# Adafruit_DPI_Kippah.net
KiCad netlist of a schematic drawn in EAGLE
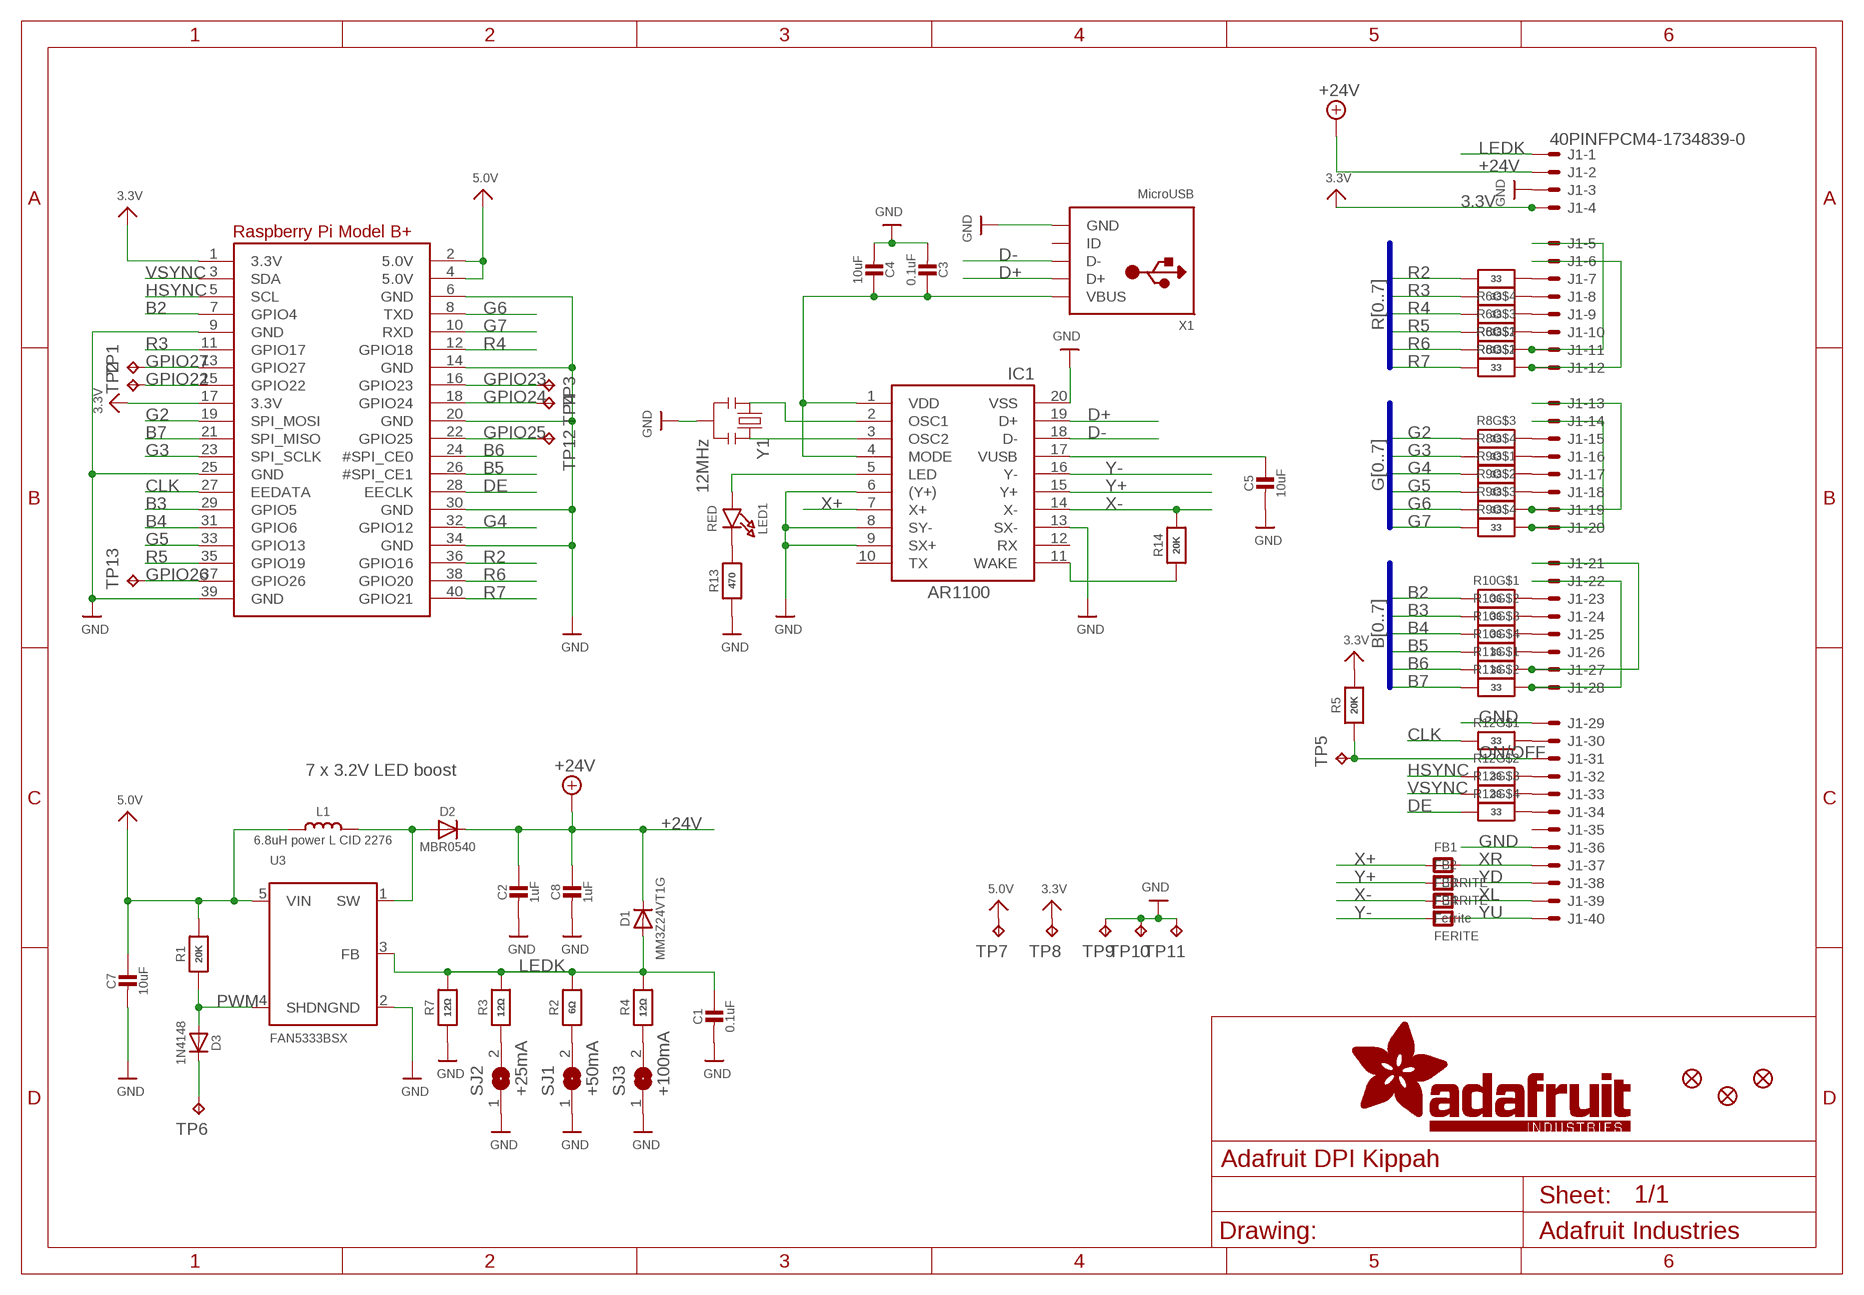
[diagram p0: schematic, sheet 1]

(export (version "E")
  (design (tool "Eeschema 10.0.6"))
  (components
    (comp (ref "C1")
      (value "0.1uF")
      (footprint "eagle-import:0805-NO")
      (libsource (lib "eagle-import") (part "CAP_CERAMIC0805-NOOUTLINE"))
    )
    (comp (ref "C2")
      (value "1uF")
      (footprint "eagle-import:_0805MP")
      (libsource (lib "eagle-import") (part "CAP_CERAMIC_0805MP"))
    )
    (comp (ref "C3")
      (value "0.1uF")
      (footprint "eagle-import:0805-NO")
      (libsource (lib "eagle-import") (part "CAP_CERAMIC0805-NOOUTLINE"))
    )
    (comp (ref "C4")
      (value "10uF")
      (footprint "eagle-import:0805-NO")
      (libsource (lib "eagle-import") (part "CAP_CERAMIC0805-NOOUTLINE"))
    )
    (comp (ref "C5")
      (value "10uF")
      (footprint "eagle-import:0805-NO")
      (libsource (lib "eagle-import") (part "CAP_CERAMIC0805-NOOUTLINE"))
    )
    (comp (ref "C7")
      (value "10uF")
      (footprint "eagle-import:0805-NO")
      (libsource (lib "eagle-import") (part "CAP_CERAMIC0805-NOOUTLINE"))
    )
    (comp (ref "C8")
      (value "1uF")
      (footprint "eagle-import:0805-NO")
      (libsource (lib "eagle-import") (part "CAP_CERAMIC0805-NOOUTLINE"))
    )
    (comp (ref "D1")
      (value "MM3Z24VT1G")
      (footprint "eagle-import:SMADIODE")
      (libsource (lib "eagle-import") (part "DIODESMA"))
    )
    (comp (ref "D2")
      (value "MBR0540")
      (footprint "eagle-import:SOD-123")
      (libsource (lib "eagle-import") (part "DIODESOD-123"))
    )
    (comp (ref "D3")
      (value "1N4148")
      (footprint "eagle-import:SOD-323")
      (libsource (lib "eagle-import") (part "DIODESOD-323"))
    )
    (comp (ref "FB1")
      (value "FERRITE")
      (footprint "eagle-import:_0805MP")
      (libsource (lib "eagle-import") (part "FERRITE_0805MP"))
    )
    (comp (ref "FB2")
      (value "FERRITE")
      (footprint "eagle-import:_0805MP")
      (libsource (lib "eagle-import") (part "FERRITE_0805MP"))
    )
    (comp (ref "FB3")
      (value "Ferrite")
      (footprint "eagle-import:_0805MP")
      (libsource (lib "eagle-import") (part "FERRITE_0805MP"))
    )
    (comp (ref "FB4")
      (value "FERITE")
      (footprint "eagle-import:_0805MP")
      (libsource (lib "eagle-import") (part "FERRITE_0805MP"))
    )
    (comp (ref "FID1")
      (value "FIDUCIAL\"\"")
      (footprint "eagle-import:FIDUCIAL_1MM")
      (libsource (lib "eagle-import") (part "FIDUCIAL{dblquote}{dblquote}"))
    )
    (comp (ref "FID2")
      (value "FIDUCIAL\"\"")
      (footprint "eagle-import:FIDUCIAL_1MM")
      (libsource (lib "eagle-import") (part "FIDUCIAL{dblquote}{dblquote}"))
    )
    (comp (ref "FID3")
      (value "FIDUCIAL\"\"")
      (footprint "eagle-import:FIDUCIAL_1MM")
      (libsource (lib "eagle-import") (part "FIDUCIAL{dblquote}{dblquote}"))
    )
    (comp (ref "IC1")
      (value "AR1100_SSOP")
      (footprint "eagle-import:TSSOP20-5.3MMBODY")
      (libsource (lib "eagle-import") (part "AR1100_SSOP"))
    )
    (comp (ref "J1")
      (value "40PINFPCM4-1734839-0")
      (footprint "eagle-import:4-1734839-0")
      (libsource (lib "eagle-import") (part "40PINFPC4-1734839-0M"))
    )
    (comp (ref "L1")
      (value "6.8uH power L CID 2276")
      (footprint "eagle-import:INDUCTOR_5X5MM_NR5040_NOTHERMALS")
      (libsource (lib "eagle-import") (part "INDUCTORNR5040"))
    )
    (comp (ref "LED1")
      (value "RED")
      (footprint "eagle-import:CHIPLED_0805_NOOUTLINE")
      (libsource (lib "eagle-import") (part "LED0805_NOOUTLINE"))
    )
    (comp (ref "R1")
      (value "20K")
      (footprint "eagle-import:0805-NO")
      (libsource (lib "eagle-import") (part "RESISTOR0805_NOOUTLINE"))
    )
    (comp (ref "R2")
      (value "6Ω")
      (footprint "eagle-import:0805-NO")
      (libsource (lib "eagle-import") (part "RESISTOR0805_NOOUTLINE"))
    )
    (comp (ref "R3")
      (value "12Ω")
      (footprint "eagle-import:0805-NO")
      (libsource (lib "eagle-import") (part "RESISTOR0805_NOOUTLINE"))
    )
    (comp (ref "R4")
      (value "12Ω")
      (footprint "eagle-import:0805-NO")
      (libsource (lib "eagle-import") (part "RESISTOR0805_NOOUTLINE"))
    )
    (comp (ref "R5")
      (value "20K")
      (footprint "eagle-import:_0805MP")
      (libsource (lib "eagle-import") (part "RESISTOR_0805MP"))
    )
    (comp (ref "R6")
      (value "33")
      (footprint "eagle-import:RESPACK_4X0603")
      (libsource (lib "eagle-import") (part "RESISTOR_4PACK"))
    )
    (comp (ref "R7")
      (value "12Ω")
      (footprint "eagle-import:0805-NO")
      (libsource (lib "eagle-import") (part "RESISTOR0805_NOOUTLINE"))
    )
    (comp (ref "R8")
      (value "33")
      (footprint "eagle-import:RESPACK_4X0603")
      (libsource (lib "eagle-import") (part "RESISTOR_4PACK"))
    )
    (comp (ref "R9")
      (value "33")
      (footprint "eagle-import:RESPACK_4X0603")
      (libsource (lib "eagle-import") (part "RESISTOR_4PACK"))
    )
    (comp (ref "R10")
      (value "33")
      (footprint "eagle-import:RESPACK_4X0603")
      (libsource (lib "eagle-import") (part "RESISTOR_4PACK"))
    )
    (comp (ref "R11")
      (value "33")
      (footprint "eagle-import:RESPACK_4X0603")
      (libsource (lib "eagle-import") (part "RESISTOR_4PACK"))
    )
    (comp (ref "R12")
      (value "33")
      (footprint "eagle-import:RESPACK_4X0603")
      (libsource (lib "eagle-import") (part "RESISTOR_4PACK"))
    )
    (comp (ref "R13")
      (value "470")
      (footprint "eagle-import:0805-NO")
      (libsource (lib "eagle-import") (part "RESISTOR0805_NOOUTLINE"))
    )
    (comp (ref "R14")
      (value "20K")
      (footprint "eagle-import:0805-NO")
      (libsource (lib "eagle-import") (part "RESISTOR0805_NOOUTLINE"))
    )
    (comp (ref "RPI1")
      (value "RASPBERRYPI_BPLUS-SMT+SLOTS")
      (footprint "eagle-import:PI_HAT_SMT_SLOTS")
      (libsource (lib "eagle-import") (part "RASPBERRYPI_BPLUS-SMT+SLOTS"))
    )
    (comp (ref "SJ1")
      (value "+50mA")
      (footprint "eagle-import:SOLDERJUMPER_ARROW_NOPASTE")
      (libsource (lib "eagle-import") (part "SOLDERJUMPER"))
    )
    (comp (ref "SJ2")
      (value "+25mA")
      (footprint "eagle-import:SOLDERJUMPER_ARROW_NOPASTE")
      (libsource (lib "eagle-import") (part "SOLDERJUMPER"))
    )
    (comp (ref "SJ3")
      (value "+100mA")
      (footprint "eagle-import:SOLDERJUMPER_ARROW_NOPASTE")
      (libsource (lib "eagle-import") (part "SOLDERJUMPER"))
    )
    (comp (ref "TP1")
      (value "TPTP15SQ")
      (footprint "eagle-import:TP15SQ")
      (libsource (lib "eagle-import") (part "TPTP15SQ"))
    )
    (comp (ref "TP2")
      (value "TPTP15SQ")
      (footprint "eagle-import:TP15SQ")
      (libsource (lib "eagle-import") (part "TPTP15SQ"))
    )
    (comp (ref "TP3")
      (value "TPTP15SQ")
      (footprint "eagle-import:TP15SQ")
      (libsource (lib "eagle-import") (part "TPTP15SQ"))
    )
    (comp (ref "TP4")
      (value "TPTP15SQ")
      (footprint "eagle-import:TP15SQ")
      (libsource (lib "eagle-import") (part "TPTP15SQ"))
    )
    (comp (ref "TP5")
      (value "TPTP15SQ")
      (footprint "eagle-import:TP15SQ")
      (libsource (lib "eagle-import") (part "TPTP15SQ"))
    )
    (comp (ref "TP6")
      (value "TPTP15SQ")
      (footprint "eagle-import:TP15SQ")
      (libsource (lib "eagle-import") (part "TPTP15SQ"))
    )
    (comp (ref "TP7")
      (value "TPTP15SQ")
      (footprint "eagle-import:TP15SQ")
      (libsource (lib "eagle-import") (part "TPTP15SQ"))
    )
    (comp (ref "TP8")
      (value "TPTP15SQ")
      (footprint "eagle-import:TP15SQ")
      (libsource (lib "eagle-import") (part "TPTP15SQ"))
    )
    (comp (ref "TP9")
      (value "TPTP15SQ")
      (footprint "eagle-import:TP15SQ")
      (libsource (lib "eagle-import") (part "TPTP15SQ"))
    )
    (comp (ref "TP10")
      (value "TPTP15SQ")
      (footprint "eagle-import:TP15SQ")
      (libsource (lib "eagle-import") (part "TPTP15SQ"))
    )
    (comp (ref "TP11")
      (value "TPTP15SQ")
      (footprint "eagle-import:TP15SQ")
      (libsource (lib "eagle-import") (part "TPTP15SQ"))
    )
    (comp (ref "TP12")
      (value "TPTP15SQ")
      (footprint "eagle-import:TP15SQ")
      (libsource (lib "eagle-import") (part "TPTP15SQ"))
    )
    (comp (ref "TP13")
      (value "TPTP15SQ")
      (footprint "eagle-import:TP15SQ")
      (libsource (lib "eagle-import") (part "TPTP15SQ"))
    )
    (comp (ref "U3")
      (value "FAN5333BSX")
      (footprint "eagle-import:SOT23-5@1")
      (libsource (lib "eagle-import") (part "FAN5331"))
    )
    (comp (ref "X1")
      (value "MicroUSB")
      (footprint "eagle-import:4UCONN_20329")
      (libsource (lib "eagle-import") (part "USBMICRO_20329"))
    )
    (comp (ref "Y1")
      (value "12MHz")
      (footprint "eagle-import:RESONATOR-SMD")
      (libsource (lib "eagle-import") (part "RESONATORSMD"))
    )
  )
  (nets
    (net (code "7") (name "+24V") (class "Default")
      (node (ref "C2") (pin "1") (pinfunction "1_1") (pintype "passive"))
      (node (ref "C8") (pin "1") (pinfunction "1_1") (pintype "passive"))
      (node (ref "D1") (pin "C") (pinfunction "C_C") (pintype "passive"))
      (node (ref "D2") (pin "C") (pinfunction "C_C") (pintype "passive"))
      (node (ref "J1") (pin "2") (pinfunction "MS_2") (pintype "passive"))
    )
    (net (code "8") (name "/B2") (class "Default")
      (node (ref "R10") (pin "1") (pinfunction "1_1") (pintype "passive"))
      (node (ref "RPI1") (pin "7") (pinfunction "GPIO4_7") (pintype "bidirectional"))
    )
    (net (code "9") (name "/B3") (class "Default")
      (node (ref "R10") (pin "2") (pinfunction "1_2") (pintype "passive"))
      (node (ref "RPI1") (pin "29") (pinfunction "GPIO5_29") (pintype "bidirectional"))
    )
    (net (code "10") (name "/B4") (class "Default")
      (node (ref "R10") (pin "3") (pinfunction "1_3") (pintype "passive"))
      (node (ref "RPI1") (pin "31") (pinfunction "GPIO6_31") (pintype "bidirectional"))
    )
    (net (code "11") (name "/B5") (class "Default")
      (node (ref "R10") (pin "4") (pinfunction "1_4") (pintype "passive"))
      (node (ref "RPI1") (pin "26") (pinfunction "#SPI_CE1_26") (pintype "bidirectional"))
    )
    (net (code "12") (name "/B6") (class "Default")
      (node (ref "R11") (pin "1") (pinfunction "1_1") (pintype "passive"))
      (node (ref "RPI1") (pin "24") (pinfunction "#SPI_CE0_24") (pintype "bidirectional"))
    )
    (net (code "13") (name "/B7") (class "Default")
      (node (ref "R11") (pin "2") (pinfunction "1_2") (pintype "passive"))
      (node (ref "RPI1") (pin "21") (pinfunction "SPI_MISO_21") (pintype "bidirectional"))
    )
    (net (code "15") (name "/CLK") (class "Default")
      (node (ref "R12") (pin "1") (pinfunction "1_1") (pintype "passive"))
      (node (ref "RPI1") (pin "27") (pinfunction "EEDATA_27") (pintype "bidirectional"))
    )
    (net (code "16") (name "/D+") (class "Default")
      (node (ref "IC1") (pin "19") (pinfunction "D+_19") (pintype "bidirectional"))
      (node (ref "X1") (pin "D+") (pinfunction "D+_D+") (pintype "bidirectional"))
    )
    (net (code "17") (name "/D-") (class "Default")
      (node (ref "IC1") (pin "18") (pinfunction "D-_18") (pintype "bidirectional"))
      (node (ref "X1") (pin "D-") (pinfunction "D-_D-") (pintype "bidirectional"))
    )
    (net (code "18") (name "/DE") (class "Default")
      (node (ref "R12") (pin "4") (pinfunction "1_4") (pintype "passive"))
      (node (ref "RPI1") (pin "28") (pinfunction "EECLK_28") (pintype "bidirectional"))
    )
    (net (code "19") (name "/G2") (class "Default")
      (node (ref "R8") (pin "3") (pinfunction "1_3") (pintype "passive"))
      (node (ref "RPI1") (pin "19") (pinfunction "SPI_MOSI_19") (pintype "bidirectional"))
    )
    (net (code "20") (name "/G3") (class "Default")
      (node (ref "R8") (pin "4") (pinfunction "1_4") (pintype "passive"))
      (node (ref "RPI1") (pin "23") (pinfunction "SPI_SCLK_23") (pintype "bidirectional"))
    )
    (net (code "21") (name "/G4") (class "Default")
      (node (ref "R9") (pin "1") (pinfunction "1_1") (pintype "passive"))
      (node (ref "RPI1") (pin "32") (pinfunction "GPIO12_32") (pintype "bidirectional"))
    )
    (net (code "22") (name "/G5") (class "Default")
      (node (ref "R9") (pin "2") (pinfunction "1_2") (pintype "passive"))
      (node (ref "RPI1") (pin "33") (pinfunction "GPIO13_33") (pintype "bidirectional"))
    )
    (net (code "23") (name "/G6") (class "Default")
      (node (ref "R9") (pin "3") (pinfunction "1_3") (pintype "passive"))
      (node (ref "RPI1") (pin "8") (pinfunction "TXD_8") (pintype "bidirectional"))
    )
    (net (code "24") (name "/G7") (class "Default")
      (node (ref "R9") (pin "4") (pinfunction "1_4") (pintype "passive"))
      (node (ref "RPI1") (pin "10") (pinfunction "RXD_10") (pintype "bidirectional"))
    )
    (net (code "25") (name "/GPIO22") (class "Default")
      (node (ref "RPI1") (pin "15") (pinfunction "GPIO22_15") (pintype "bidirectional"))
      (node (ref "TP2") (pin "TP") (pinfunction "TP_TP") (pintype "input"))
    )
    (net (code "26") (name "/GPIO23") (class "Default")
      (node (ref "RPI1") (pin "16") (pinfunction "GPIO23_16") (pintype "bidirectional"))
      (node (ref "TP3") (pin "TP") (pinfunction "TP_TP") (pintype "input"))
    )
    (net (code "27") (name "/GPIO24") (class "Default")
      (node (ref "RPI1") (pin "18") (pinfunction "GPIO24_18") (pintype "bidirectional"))
      (node (ref "TP4") (pin "TP") (pinfunction "TP_TP") (pintype "input"))
    )
    (net (code "28") (name "/GPIO25") (class "Default")
      (node (ref "RPI1") (pin "22") (pinfunction "GPIO25_22") (pintype "bidirectional"))
      (node (ref "TP12") (pin "TP") (pinfunction "TP_TP") (pintype "input"))
    )
    (net (code "29") (name "/GPIO26") (class "Default")
      (node (ref "RPI1") (pin "37") (pinfunction "GPIO26_37") (pintype "bidirectional"))
      (node (ref "TP13") (pin "TP") (pinfunction "TP_TP") (pintype "input"))
    )
    (net (code "30") (name "/GPIO27") (class "Default")
      (node (ref "RPI1") (pin "13") (pinfunction "GPIO27_13") (pintype "bidirectional"))
      (node (ref "TP1") (pin "TP") (pinfunction "TP_TP") (pintype "input"))
    )
    (net (code "32") (name "/HSYNC") (class "Default")
      (node (ref "R12") (pin "2") (pinfunction "1_2") (pintype "passive"))
      (node (ref "RPI1") (pin "5") (pinfunction "SCL_5") (pintype "bidirectional"))
    )
    (net (code "33") (name "/LEDK") (class "Default")
      (node (ref "C1") (pin "1") (pinfunction "1_1") (pintype "passive"))
      (node (ref "D1") (pin "A") (pinfunction "A_A") (pintype "passive"))
      (node (ref "J1") (pin "1") (pinfunction "MSV_1") (pintype "passive"))
      (node (ref "R2") (pin "2") (pinfunction "2_2") (pintype "passive"))
      (node (ref "R3") (pin "2") (pinfunction "2_2") (pintype "passive"))
      (node (ref "R4") (pin "2") (pinfunction "2_2") (pintype "passive"))
      (node (ref "R7") (pin "2") (pinfunction "2_2") (pintype "passive"))
      (node (ref "U3") (pin "3") (pinfunction "FB_3") (pintype "bidirectional"))
    )
    (net (code "34") (name "/ON{slash}OFF") (class "Default")
      (node (ref "J1") (pin "31") (pinfunction "MS_31") (pintype "passive"))
      (node (ref "R5") (pin "1") (pinfunction "1_1") (pintype "passive"))
      (node (ref "TP5") (pin "TP") (pinfunction "TP_TP") (pintype "input"))
    )
    (net (code "35") (name "/PWM") (class "Default")
      (node (ref "D3") (pin "A") (pinfunction "A_A") (pintype "passive"))
      (node (ref "R1") (pin "1") (pinfunction "1_1") (pintype "passive"))
      (node (ref "U3") (pin "4") (pinfunction "SHDN_4") (pintype "bidirectional"))
    )
    (net (code "36") (name "/R2") (class "Default")
      (node (ref "R6") (pin "5") (pinfunction "2_5") (pintype "passive"))
      (node (ref "RPI1") (pin "36") (pinfunction "GPIO16_36") (pintype "bidirectional"))
    )
    (net (code "37") (name "/R3") (class "Default")
      (node (ref "R6") (pin "6") (pinfunction "2_6") (pintype "passive"))
      (node (ref "RPI1") (pin "11") (pinfunction "GPIO17_11") (pintype "bidirectional"))
    )
    (net (code "38") (name "/R4") (class "Default")
      (node (ref "R6") (pin "7") (pinfunction "2_7") (pintype "passive"))
      (node (ref "RPI1") (pin "12") (pinfunction "GPIO18_12") (pintype "bidirectional"))
    )
    (net (code "39") (name "/R5") (class "Default")
      (node (ref "R6") (pin "8") (pinfunction "2_8") (pintype "passive"))
      (node (ref "RPI1") (pin "35") (pinfunction "GPIO19_35") (pintype "bidirectional"))
    )
    (net (code "40") (name "/R6") (class "Default")
      (node (ref "R8") (pin "1") (pinfunction "1_1") (pintype "passive"))
      (node (ref "RPI1") (pin "38") (pinfunction "GPIO20_38") (pintype "bidirectional"))
    )
    (net (code "41") (name "/R7") (class "Default")
      (node (ref "R8") (pin "2") (pinfunction "1_2") (pintype "passive"))
      (node (ref "RPI1") (pin "40") (pinfunction "GPIO21_40") (pintype "bidirectional"))
    )
    (net (code "43") (name "/VSYNC") (class "Default")
      (node (ref "R12") (pin "3") (pinfunction "1_3") (pintype "passive"))
      (node (ref "RPI1") (pin "3") (pinfunction "SDA_3") (pintype "bidirectional"))
    )
    (net (code "44") (name "/X+") (class "Default")
      (node (ref "FB1") (pin "1") (pinfunction "P$1_1") (pintype "passive"))
      (node (ref "IC1") (pin "7") (pinfunction "X+_7") (pintype "bidirectional"))
    )
    (net (code "45") (name "/X-") (class "Default")
      (node (ref "FB3") (pin "1") (pinfunction "P$1_1") (pintype "passive"))
      (node (ref "IC1") (pin "14") (pinfunction "X-_14") (pintype "bidirectional"))
      (node (ref "R14") (pin "2") (pinfunction "2_2") (pintype "passive"))
    )
    (net (code "46") (name "/XL") (class "Default")
      (node (ref "FB3") (pin "2") (pinfunction "P$2_2") (pintype "passive"))
      (node (ref "J1") (pin "39") (pinfunction "MS_39") (pintype "passive"))
    )
    (net (code "47") (name "/XR") (class "Default")
      (node (ref "FB1") (pin "2") (pinfunction "P$2_2") (pintype "passive"))
      (node (ref "J1") (pin "37") (pinfunction "MS_37") (pintype "passive"))
    )
    (net (code "48") (name "/Y+") (class "Default")
      (node (ref "FB2") (pin "1") (pinfunction "P$1_1") (pintype "passive"))
      (node (ref "IC1") (pin "15") (pinfunction "Y+_15") (pintype "bidirectional"))
    )
    (net (code "49") (name "/Y-") (class "Default")
      (node (ref "FB4") (pin "1") (pinfunction "P$1_1") (pintype "passive"))
      (node (ref "IC1") (pin "16") (pinfunction "Y-_16") (pintype "bidirectional"))
    )
    (net (code "50") (name "/YD") (class "Default")
      (node (ref "FB2") (pin "2") (pinfunction "P$2_2") (pintype "passive"))
      (node (ref "J1") (pin "38") (pinfunction "MS_38") (pintype "passive"))
    )
    (net (code "51") (name "/YU") (class "Default")
      (node (ref "FB4") (pin "2") (pinfunction "P$2_2") (pintype "passive"))
      (node (ref "J1") (pin "40") (pinfunction "MS_40") (pintype "passive"))
    )
    (net (code "52") (name "3.3V") (class "Default")
      (node (ref "J1") (pin "4") (pinfunction "MS_4") (pintype "passive"))
      (node (ref "R5") (pin "2") (pinfunction "2_2") (pintype "passive"))
      (node (ref "RPI1") (pin "1") (pinfunction "3.3V_1") (pintype "power_in"))
      (node (ref "RPI1") (pin "17") (pinfunction "3.3V_17") (pintype "power_in"))
      (node (ref "TP8") (pin "TP") (pinfunction "TP_TP") (pintype "input"))
    )
    (net (code "53") (name "5.0V") (class "Default")
      (node (ref "C7") (pin "1") (pinfunction "1_1") (pintype "passive"))
      (node (ref "L1") (pin "P$1") (pinfunction "1_P$1") (pintype "passive"))
      (node (ref "R1") (pin "2") (pinfunction "2_2") (pintype "passive"))
      (node (ref "RPI1") (pin "2") (pinfunction "5.0V_2") (pintype "power_in"))
      (node (ref "RPI1") (pin "4") (pinfunction "5.0V_4") (pintype "power_in"))
      (node (ref "TP7") (pin "TP") (pinfunction "TP_TP") (pintype "input"))
      (node (ref "U3") (pin "5") (pinfunction "VIN_5") (pintype "bidirectional"))
    )
    (net (code "54") (name "GND") (class "Default")
      (node (ref "C1") (pin "2") (pinfunction "2_2") (pintype "passive"))
      (node (ref "C2") (pin "2") (pinfunction "2_2") (pintype "passive"))
      (node (ref "C3") (pin "2") (pinfunction "2_2") (pintype "passive"))
      (node (ref "C4") (pin "2") (pinfunction "2_2") (pintype "passive"))
      (node (ref "C5") (pin "2") (pinfunction "2_2") (pintype "passive"))
      (node (ref "C7") (pin "2") (pinfunction "2_2") (pintype "passive"))
      (node (ref "C8") (pin "2") (pinfunction "2_2") (pintype "passive"))
      (node (ref "IC1") (pin "13") (pinfunction "SX-_13") (pintype "bidirectional"))
      (node (ref "IC1") (pin "20") (pinfunction "VSS_20") (pintype "power_in"))
      (node (ref "IC1") (pin "6") (pinfunction "(Y+)_6") (pintype "bidirectional"))
      (node (ref "IC1") (pin "8") (pinfunction "SY-_8") (pintype "bidirectional"))
      (node (ref "IC1") (pin "9") (pinfunction "SX+_9") (pintype "bidirectional"))
      (node (ref "J1") (pin "29") (pinfunction "MS_29") (pintype "passive"))
      (node (ref "J1") (pin "3") (pinfunction "MS_3") (pintype "passive"))
      (node (ref "J1") (pin "36") (pinfunction "MS_36") (pintype "passive"))
      (node (ref "R13") (pin "1") (pinfunction "1_1") (pintype "passive"))
      (node (ref "R7") (pin "1") (pinfunction "1_1") (pintype "passive"))
      (node (ref "RPI1") (pin "14") (pinfunction "GND_14") (pintype "power_in"))
      (node (ref "RPI1") (pin "20") (pinfunction "GND_20") (pintype "power_in"))
      (node (ref "RPI1") (pin "25") (pinfunction "GND_25") (pintype "power_in"))
      (node (ref "RPI1") (pin "30") (pinfunction "GND_30") (pintype "power_in"))
      (node (ref "RPI1") (pin "34") (pinfunction "GND_34") (pintype "power_in"))
      (node (ref "RPI1") (pin "39") (pinfunction "GND_39") (pintype "power_in"))
      (node (ref "RPI1") (pin "6") (pinfunction "GND_6") (pintype "power_in"))
      (node (ref "RPI1") (pin "9") (pinfunction "GND_9") (pintype "power_in"))
      (node (ref "SJ1") (pin "1") (pinfunction "1_1") (pintype "passive"))
      (node (ref "SJ2") (pin "1") (pinfunction "1_1") (pintype "passive"))
      (node (ref "SJ3") (pin "1") (pinfunction "1_1") (pintype "passive"))
      (node (ref "TP10") (pin "TP") (pinfunction "TP_TP") (pintype "input"))
      (node (ref "TP11") (pin "TP") (pinfunction "TP_TP") (pintype "input"))
      (node (ref "TP9") (pin "TP") (pinfunction "TP_TP") (pintype "input"))
      (node (ref "U3") (pin "2") (pinfunction "GND_2") (pintype "bidirectional"))
      (node (ref "X1") (pin "BASE@1") (pinfunction "GND_BASE@1") (pintype "power_in"))
      (node (ref "X1") (pin "BASE@2") (pinfunction "GND_BASE@2") (pintype "power_in"))
      (node (ref "X1") (pin "GND") (pinfunction "GND_GND") (pintype "power_in"))
      (node (ref "X1") (pin "SPRT@1") (pinfunction "GND_SPRT@1") (pintype "power_in"))
      (node (ref "X1") (pin "SPRT@2") (pinfunction "GND_SPRT@2") (pintype "power_in"))
      (node (ref "X1") (pin "SPRT@3") (pinfunction "GND_SPRT@3") (pintype "power_in"))
      (node (ref "X1") (pin "SPRT@4") (pinfunction "GND_SPRT@4") (pintype "power_in"))
      (node (ref "Y1") (pin "2") (pinfunction "2_2") (pintype "passive"))
    )
    (net (code "55") (name "Net-(D3-PadC)") (class "Default")
      (node (ref "D3") (pin "C") (pinfunction "C_C") (pintype "passive"))
      (node (ref "TP6") (pin "TP") (pinfunction "TP_TP") (pintype "input"))
    )
    (net (code "56") (name "Net-(IC1-LED)") (class "Default")
      (node (ref "IC1") (pin "5") (pinfunction "LED_5") (pintype "output"))
      (node (ref "LED1") (pin "A") (pinfunction "A_A") (pintype "passive"))
    )
    (net (code "57") (name "Net-(IC1-MODE)") (class "Default")
      (node (ref "C3") (pin "1") (pinfunction "1_1") (pintype "passive"))
      (node (ref "C4") (pin "1") (pinfunction "1_1") (pintype "passive"))
      (node (ref "IC1") (pin "1") (pinfunction "VDD_1") (pintype "power_in"))
      (node (ref "IC1") (pin "4") (pinfunction "MODE_4") (pintype "input"))
      (node (ref "X1") (pin "VBUS") (pinfunction "VBUS_VBUS") (pintype "power_in"))
    )
    (net (code "58") (name "Net-(IC1-OSC1)") (class "Default")
      (node (ref "IC1") (pin "2") (pinfunction "OSC1_2") (pintype "passive"))
      (node (ref "Y1") (pin "1") (pinfunction "1_1") (pintype "passive"))
    )
    (net (code "59") (name "Net-(IC1-OSC2)") (class "Default")
      (node (ref "IC1") (pin "3") (pinfunction "OSC2_3") (pintype "passive"))
      (node (ref "Y1") (pin "3") (pinfunction "3_3") (pintype "passive"))
    )
    (net (code "60") (name "Net-(IC1-VUSB)") (class "Default")
      (node (ref "C5") (pin "1") (pinfunction "1_1") (pintype "passive"))
      (node (ref "IC1") (pin "17") (pinfunction "VUSB_17") (pintype "power_in"))
    )
    (net (code "61") (name "Net-(IC1-WAKE)") (class "Default")
      (node (ref "IC1") (pin "11") (pinfunction "WAKE_11") (pintype "input"))
      (node (ref "R14") (pin "1") (pinfunction "1_1") (pintype "passive"))
    )
    (net (code "62") (name "Net-(J1AA-MS)") (class "Default")
      (node (ref "J1") (pin "33") (pinfunction "MS_33") (pintype "passive"))
      (node (ref "R12") (pin "6") (pinfunction "2_6") (pintype "passive"))
    )
    (net (code "63") (name "Net-(J1AB-MS)") (class "Default")
      (node (ref "J1") (pin "34") (pinfunction "MS_34") (pintype "passive"))
      (node (ref "R12") (pin "5") (pinfunction "2_5") (pintype "passive"))
    )
    (net (code "64") (name "Net-(J1AJ-MS)") (class "Default")
      (node (ref "J1") (pin "11") (pinfunction "MS_11") (pintype "passive"))
      (node (ref "J1") (pin "5") (pinfunction "MS_5") (pintype "passive"))
      (node (ref "R8") (pin "8") (pinfunction "2_8") (pintype "passive"))
    )
    (net (code "65") (name "Net-(J1AK-MS)") (class "Default")
      (node (ref "J1") (pin "12") (pinfunction "MS_12") (pintype "passive"))
      (node (ref "J1") (pin "6") (pinfunction "MS_6") (pintype "passive"))
      (node (ref "R8") (pin "7") (pinfunction "2_7") (pintype "passive"))
    )
    (net (code "66") (name "Net-(J1AL-MS)") (class "Default")
      (node (ref "J1") (pin "7") (pinfunction "MS_7") (pintype "passive"))
      (node (ref "R6") (pin "4") (pinfunction "1_4") (pintype "passive"))
    )
    (net (code "67") (name "Net-(J1AM-MS)") (class "Default")
      (node (ref "J1") (pin "8") (pinfunction "MS_8") (pintype "passive"))
      (node (ref "R6") (pin "3") (pinfunction "1_3") (pintype "passive"))
    )
    (net (code "68") (name "Net-(J1AN-MS)") (class "Default")
      (node (ref "J1") (pin "9") (pinfunction "MS_9") (pintype "passive"))
      (node (ref "R6") (pin "2") (pinfunction "1_2") (pintype "passive"))
    )
    (net (code "69") (name "Net-(J1B-MS)") (class "Default")
      (node (ref "J1") (pin "10") (pinfunction "MS_10") (pintype "passive"))
      (node (ref "R6") (pin "1") (pinfunction "1_1") (pintype "passive"))
    )
    (net (code "70") (name "Net-(J1E-MS)") (class "Default")
      (node (ref "J1") (pin "13") (pinfunction "MS_13") (pintype "passive"))
      (node (ref "J1") (pin "19") (pinfunction "MS_19") (pintype "passive"))
      (node (ref "R9") (pin "6") (pinfunction "2_6") (pintype "passive"))
    )
    (net (code "71") (name "Net-(J1F-MS)") (class "Default")
      (node (ref "J1") (pin "14") (pinfunction "MS_14") (pintype "passive"))
      (node (ref "J1") (pin "20") (pinfunction "MS_20") (pintype "passive"))
      (node (ref "R9") (pin "5") (pinfunction "2_5") (pintype "passive"))
    )
    (net (code "72") (name "Net-(J1G-MS)") (class "Default")
      (node (ref "J1") (pin "15") (pinfunction "MS_15") (pintype "passive"))
      (node (ref "R8") (pin "6") (pinfunction "2_6") (pintype "passive"))
    )
    (net (code "73") (name "Net-(J1H-MS)") (class "Default")
      (node (ref "J1") (pin "16") (pinfunction "MS_16") (pintype "passive"))
      (node (ref "R8") (pin "5") (pinfunction "2_5") (pintype "passive"))
    )
    (net (code "74") (name "Net-(J1I-MS)") (class "Default")
      (node (ref "J1") (pin "17") (pinfunction "MS_17") (pintype "passive"))
      (node (ref "R9") (pin "8") (pinfunction "2_8") (pintype "passive"))
    )
    (net (code "75") (name "Net-(J1J-MS)") (class "Default")
      (node (ref "J1") (pin "18") (pinfunction "MS_18") (pintype "passive"))
      (node (ref "R9") (pin "7") (pinfunction "2_7") (pintype "passive"))
    )
    (net (code "76") (name "Net-(J1N-MS)") (class "Default")
      (node (ref "J1") (pin "21") (pinfunction "MS_21") (pintype "passive"))
      (node (ref "J1") (pin "27") (pinfunction "MS_27") (pintype "passive"))
      (node (ref "R11") (pin "8") (pinfunction "2_8") (pintype "passive"))
    )
    (net (code "77") (name "Net-(J1O-MS)") (class "Default")
      (node (ref "J1") (pin "22") (pinfunction "MS_22") (pintype "passive"))
      (node (ref "J1") (pin "28") (pinfunction "MS_28") (pintype "passive"))
      (node (ref "R11") (pin "7") (pinfunction "2_7") (pintype "passive"))
    )
    (net (code "78") (name "Net-(J1P-MS)") (class "Default")
      (node (ref "J1") (pin "23") (pinfunction "MS_23") (pintype "passive"))
      (node (ref "R10") (pin "8") (pinfunction "2_8") (pintype "passive"))
    )
    (net (code "79") (name "Net-(J1Q-MS)") (class "Default")
      (node (ref "J1") (pin "24") (pinfunction "MS_24") (pintype "passive"))
      (node (ref "R10") (pin "7") (pinfunction "2_7") (pintype "passive"))
    )
    (net (code "80") (name "Net-(J1R-MS)") (class "Default")
      (node (ref "J1") (pin "25") (pinfunction "MS_25") (pintype "passive"))
      (node (ref "R10") (pin "6") (pinfunction "2_6") (pintype "passive"))
    )
    (net (code "81") (name "Net-(J1S-MS)") (class "Default")
      (node (ref "J1") (pin "26") (pinfunction "MS_26") (pintype "passive"))
      (node (ref "R10") (pin "5") (pinfunction "2_5") (pintype "passive"))
    )
    (net (code "82") (name "Net-(J1X-MS)") (class "Default")
      (node (ref "J1") (pin "30") (pinfunction "MS_30") (pintype "passive"))
      (node (ref "R12") (pin "8") (pinfunction "2_8") (pintype "passive"))
    )
    (net (code "83") (name "Net-(J1Z-MS)") (class "Default")
      (node (ref "J1") (pin "32") (pinfunction "MS_32") (pintype "passive"))
      (node (ref "R12") (pin "7") (pinfunction "2_7") (pintype "passive"))
    )
    (net (code "84") (name "Net-(L1-2)") (class "Default")
      (node (ref "D2") (pin "A") (pinfunction "A_A") (pintype "passive"))
      (node (ref "L1") (pin "P$2") (pinfunction "2_P$2") (pintype "passive"))
      (node (ref "U3") (pin "1") (pinfunction "SW_1") (pintype "bidirectional"))
    )
    (net (code "85") (name "Net-(LED1-PadC)") (class "Default")
      (node (ref "LED1") (pin "C") (pinfunction "C_C") (pintype "passive"))
      (node (ref "R13") (pin "2") (pinfunction "2_2") (pintype "passive"))
    )
    (net (code "86") (name "Net-(R2-Pad1)") (class "Default")
      (node (ref "R2") (pin "1") (pinfunction "1_1") (pintype "passive"))
      (node (ref "SJ1") (pin "2") (pinfunction "2_2") (pintype "passive"))
    )
    (net (code "87") (name "Net-(R3-Pad1)") (class "Default")
      (node (ref "R3") (pin "1") (pinfunction "1_1") (pintype "passive"))
      (node (ref "SJ2") (pin "2") (pinfunction "2_2") (pintype "passive"))
    )
    (net (code "88") (name "Net-(R4-Pad1)") (class "Default")
      (node (ref "R4") (pin "1") (pinfunction "1_1") (pintype "passive"))
      (node (ref "SJ3") (pin "2") (pinfunction "2_2") (pintype "passive"))
    )
    (net (code "89") (name "unconnected-(IC1-RX-Pad12)") (class "Default")
      (node (ref "IC1") (pin "12") (pinfunction "RX_12") (pintype "input"))
    )
    (net (code "90") (name "unconnected-(IC1-TX-Pad10)") (class "Default")
      (node (ref "IC1") (pin "10") (pinfunction "TX_10") (pintype "output"))
    )
    (net (code "91") (name "unconnected-(J1AC-MS-Pad35)") (class "Default")
      (node (ref "J1") (pin "35") (pinfunction "MS_35") (pintype "passive"))
    )
    (net (code "92") (name "unconnected-(X1-PadID)") (class "Default")
      (node (ref "X1") (pin "ID") (pinfunction "ID_ID") (pintype "bidirectional"))
    )
  )
)
